# HumFlex3_mech.net
KiCad netlist of a schematic drawn in Altium Designer
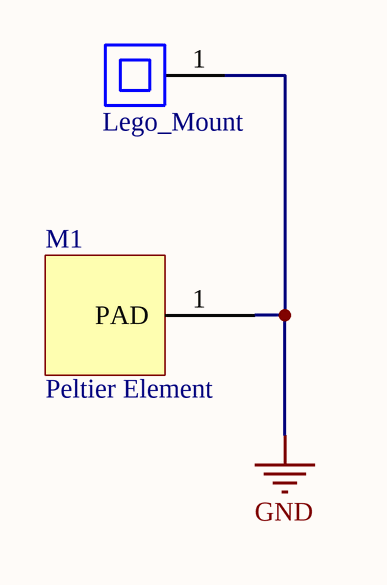
[diagram p0: HumFlex3_mech.SchDoc]

(export (version "E")
  (design (tool "Eeschema 10.0.6"))
  (components
    (comp (ref "M1")
      (value "Peltier Element")
      (footprint "PeltierElement2")
      (description "Peltier element 40mm x 40mm")
      (libsource (lib "symbols") (part "PeltierElement"))
    )
    (comp (ref "M6")
      (value "Lego_Mount")
      (footprint "Lego_Mount")
      (libsource (lib "symbols") (part "Lego_Mount"))
    )
  )
  (nets
    (net (code "1") (name "GND") (class "Default")
      (node (ref "M1") (pin "1") (pinfunction "PAD_1") (pintype "passive"))
      (node (ref "M6") (pin "1") (pintype "passive"))
    )
  )
)
